# UserInterface.net
KiCad netlist of a schematic drawn in Altium Designer
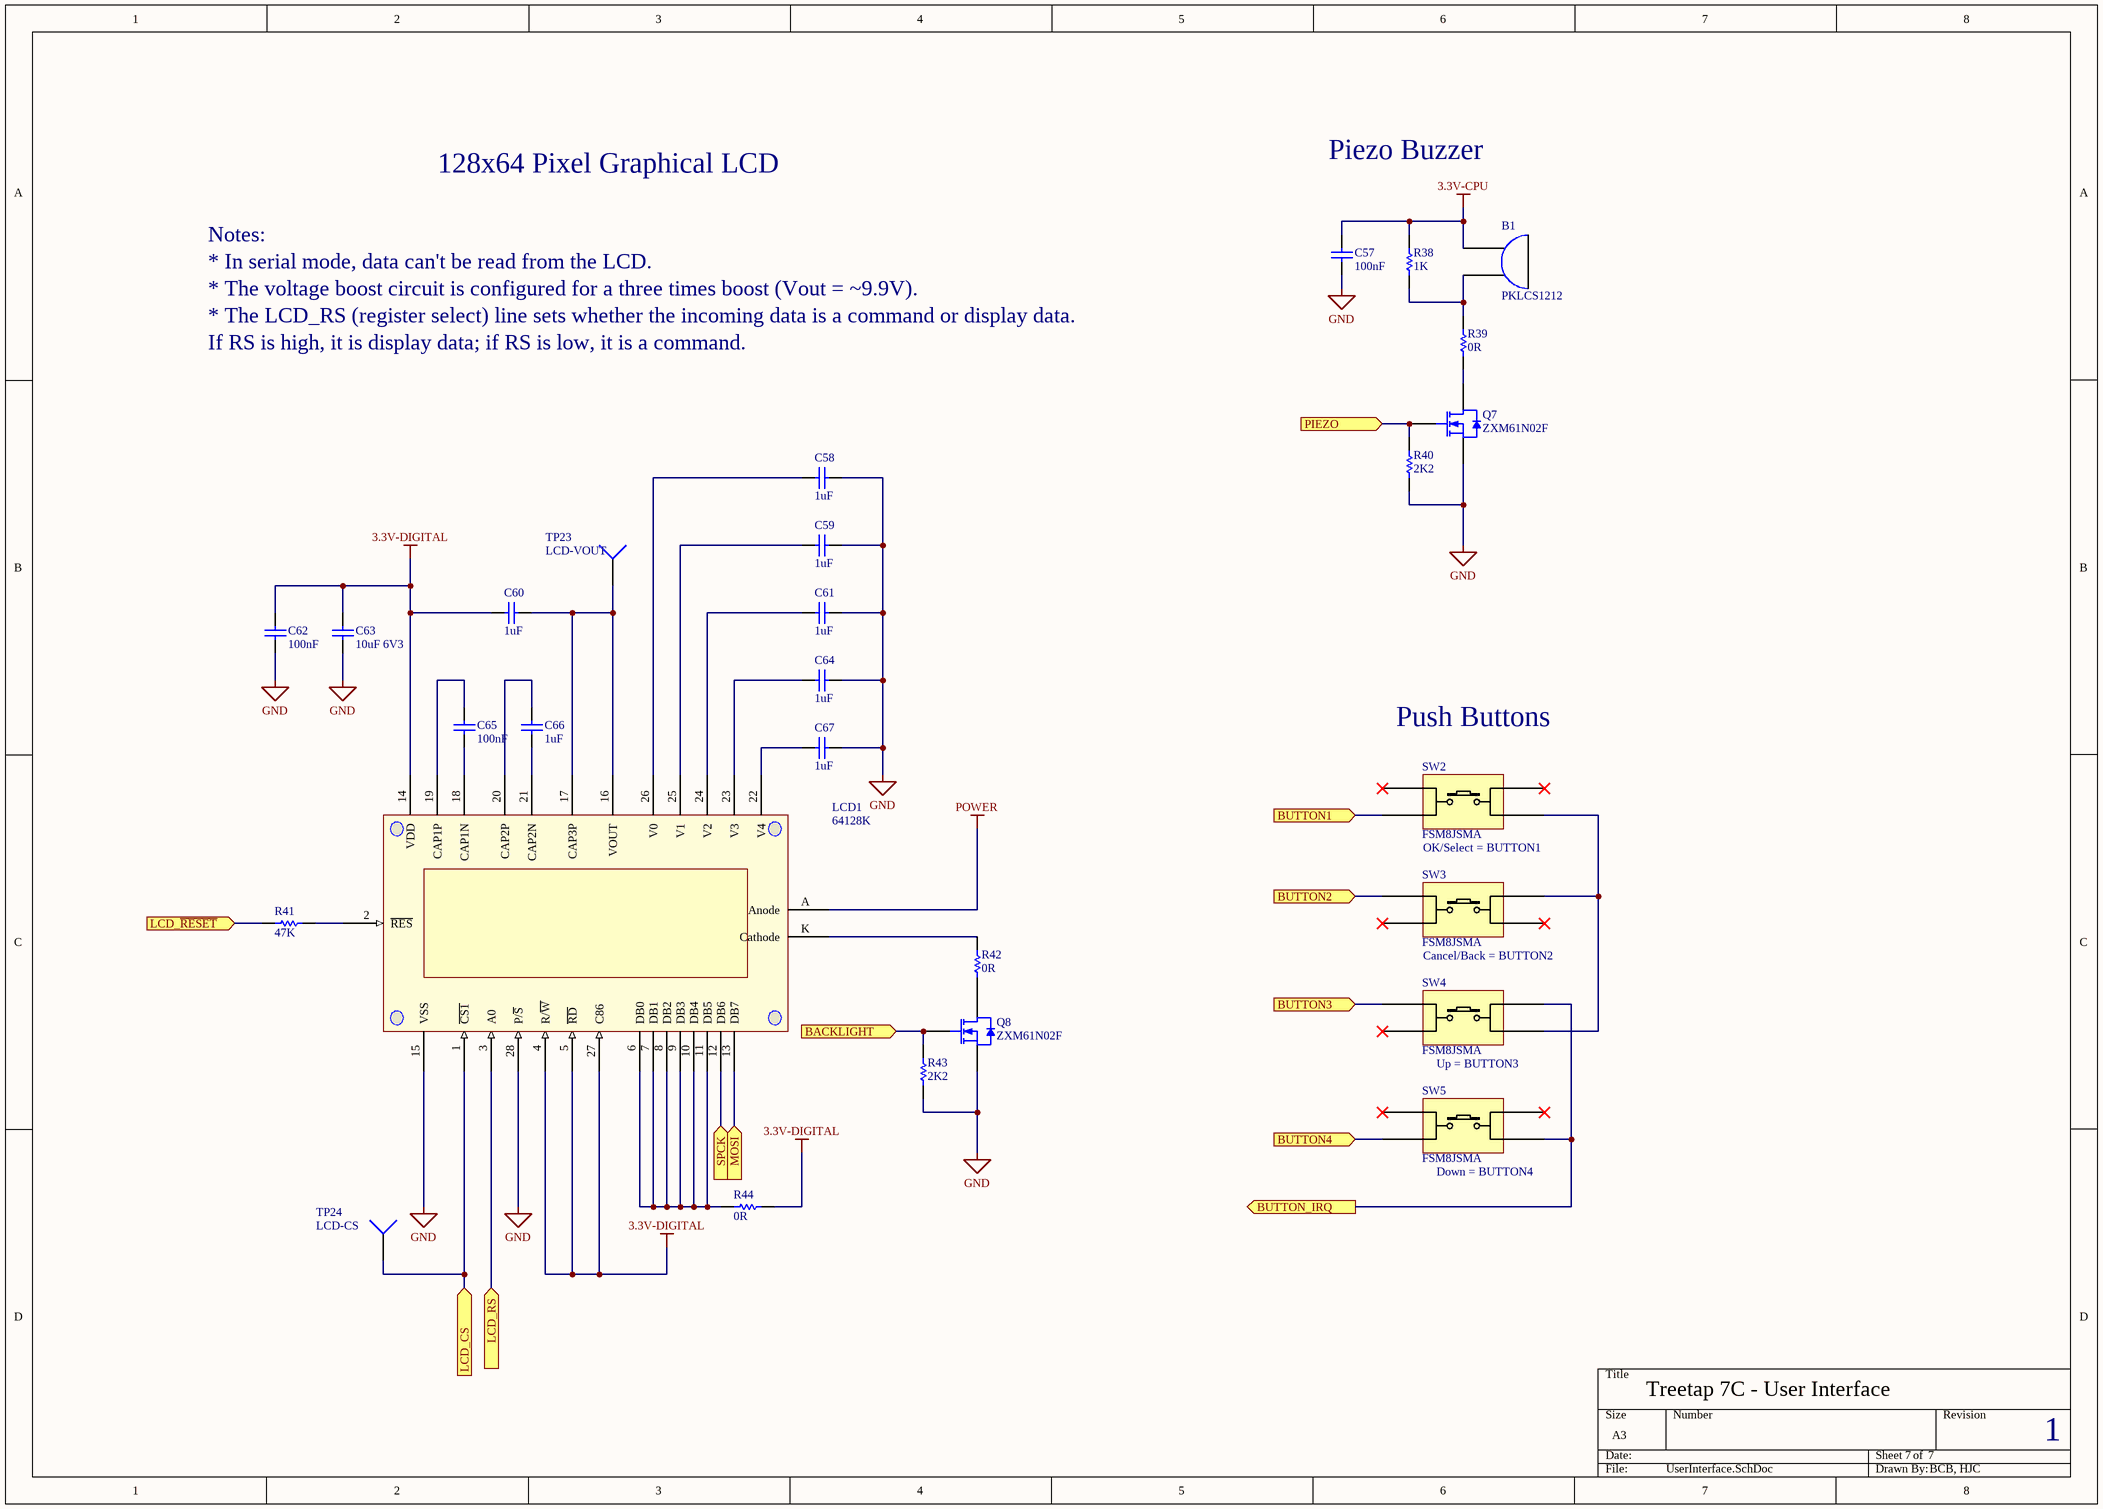
[diagram p0: UserInterface.SchDoc]

(export (version "E")
  (design (tool "Eeschema 10.0.6"))
  (components
    (comp (ref "B1")
      (value "PKLCS1212")
      (footprint "PKSCL1212")
      (description "4kHz surface mount piezo")
      (fields (field (name "MANUFACTURER") "Murata") (field (name "PART NUMBER") "PKLCS1212E4001-R1"))
      (libsource (lib "TreetapParts") (part "PKLCS1212"))
    )
    (comp (ref "C57")
      (value "100nF")
      (footprint "CC0603")
      (description "0603 Capacitor")
      (fields (field (name "PART NUMBER") "100nF_CC0603"))
      (libsource (lib "ECE_Component_Library_2") (part "100nF_CC0603"))
    )
    (comp (ref "C58")
      (value "1uF")
      (footprint "CC0603")
      (description "1uF 25V 0603 ceramic capacitor")
      (fields (field (name "MANUFACTURER") "Kemet") (field (name "PART NUMBER") "C0603C105K3PAC"))
      (libsource (lib "TreetapParts") (part "1uF_0603_25V_ceramic"))
    )
    (comp (ref "C59")
      (value "1uF")
      (footprint "CC0603")
      (description "1uF 25V 0603 ceramic capacitor")
      (fields (field (name "MANUFACTURER") "Kemet") (field (name "PART NUMBER") "C0603C105K3PAC"))
      (libsource (lib "TreetapParts") (part "1uF_0603_25V_ceramic"))
    )
    (comp (ref "C60")
      (value "1uF")
      (footprint "CC0603")
      (description "1uF 25V 0603 ceramic capacitor")
      (fields (field (name "MANUFACTURER") "Kemet") (field (name "PART NUMBER") "C0603C105K3PAC"))
      (libsource (lib "TreetapParts") (part "1uF_0603_25V_ceramic"))
    )
    (comp (ref "C61")
      (value "1uF")
      (footprint "CC0603")
      (description "1uF 25V 0603 ceramic capacitor")
      (fields (field (name "MANUFACTURER") "Kemet") (field (name "PART NUMBER") "C0603C105K3PAC"))
      (libsource (lib "TreetapParts") (part "1uF_0603_25V_ceramic"))
    )
    (comp (ref "C62")
      (value "100nF")
      (footprint "CC0603")
      (description "0603 Capacitor")
      (fields (field (name "PART NUMBER") "100nF_CC0603"))
      (libsource (lib "ECE_Component_Library_2") (part "100nF_CC0603"))
    )
    (comp (ref "C63")
      (value "10uF 6V3")
      (footprint "CC0603")
      (description "10uF 6.3V 0603 ceramic capacitor")
      (fields (field (name "MANUFACTURER") "Multicomp") (field (name "PART NUMBER") "MCCA000517"))
      (libsource (lib "TreetapParts") (part "10uF_CC0603_6V3"))
    )
    (comp (ref "C64")
      (value "1uF")
      (footprint "CC0603")
      (description "1uF 25V 0603 ceramic capacitor")
      (fields (field (name "MANUFACTURER") "Kemet") (field (name "PART NUMBER") "C0603C105K3PAC"))
      (libsource (lib "TreetapParts") (part "1uF_0603_25V_ceramic"))
    )
    (comp (ref "C65")
      (value "100nF")
      (footprint "CC0603")
      (description "0603 Capacitor")
      (fields (field (name "PART NUMBER") "100nF_CC0603"))
      (libsource (lib "ECE_Component_Library_2") (part "100nF_CC0603"))
    )
    (comp (ref "C66")
      (value "1uF")
      (footprint "CC0603")
      (description "1uF 25V 0603 ceramic capacitor")
      (fields (field (name "MANUFACTURER") "Kemet") (field (name "PART NUMBER") "C0603C105K3PAC"))
      (libsource (lib "TreetapParts") (part "1uF_0603_25V_ceramic"))
    )
    (comp (ref "C67")
      (value "1uF")
      (footprint "CC0603")
      (description "1uF 25V 0603 ceramic capacitor")
      (fields (field (name "MANUFACTURER") "Kemet") (field (name "PART NUMBER") "C0603C105K3PAC"))
      (libsource (lib "TreetapParts") (part "1uF_0603_25V_ceramic"))
    )
    (comp (ref "LCD1")
      (value "64128K")
      (footprint "64128K")
      (description "64x128 COG LCD module")
      (fields (field (name "PART NUMBER") "64128K-FC-BW-3") (field (name "MANUFACTURER") "Displaytech"))
      (libsource (lib "TreetapParts") (part "64128K"))
    )
    (comp (ref "Q7")
      (value "ZXM61N02F")
      (footprint "SOT-23")
      (description "20V N-channel enhancement mode MOSFET")
      (fields (field (name "MANUFACTURER") "Zetex"))
      (libsource (lib "TreetapParts") (part "ZXM61N02F"))
    )
    (comp (ref "Q8")
      (value "ZXM61N02F")
      (footprint "SOT-23")
      (description "20V N-channel enhancement mode MOSFET")
      (fields (field (name "MANUFACTURER") "Zetex"))
      (libsource (lib "TreetapParts") (part "ZXM61N02F"))
    )
    (comp (ref "R38")
      (value "1K")
      (footprint "R0603")
      (description "0603 Resistor")
      (fields (field (name "PART NUMBER") "1K_R0603"))
      (libsource (lib "ECE_Component_Library_2") (part "1K_R0603"))
    )
    (comp (ref "R39")
      (value "0R")
      (footprint "R0603")
      (description "0603 Resistor")
      (fields (field (name "PART NUMBER") "0R_R0603"))
      (libsource (lib "ECE_Component_Library_2") (part "0R_R0603"))
    )
    (comp (ref "R40")
      (value "2K2")
      (footprint "R0603")
      (description "0603 Resistor")
      (fields (field (name "PART NUMBER") "2K2_R0603"))
      (libsource (lib "ECE_Component_Library_2") (part "2K2_R0603"))
    )
    (comp (ref "R41")
      (value "47K")
      (footprint "R0603")
      (description "0603 Resistor")
      (fields (field (name "PART NUMBER") "47K_R0603"))
      (libsource (lib "ECE_Component_Library_2") (part "47K_R0603"))
    )
    (comp (ref "R42")
      (value "0R")
      (footprint "R0603")
      (description "0603 Resistor")
      (fields (field (name "PART NUMBER") "0R_R0603"))
      (libsource (lib "ECE_Component_Library_2") (part "0R_R0603"))
    )
    (comp (ref "R43")
      (value "2K2")
      (footprint "R0603")
      (description "0603 Resistor")
      (fields (field (name "PART NUMBER") "2K2_R0603"))
      (libsource (lib "ECE_Component_Library_2") (part "2K2_R0603"))
    )
    (comp (ref "R44")
      (value "0R")
      (footprint "R0603")
      (description "0603 Resistor")
      (fields (field (name "PART NUMBER") "0R_R0603"))
      (libsource (lib "ECE_Component_Library_2") (part "0R_R0603"))
    )
    (comp (ref "SW2")
      (value "FSM8JSMA")
      (footprint "FSM8JSMA")
      (description "DPST SMD Switch")
      (fields (field (name "MANUFACTURER") "Tyco Electronics"))
      (libsource (lib "TreetapParts") (part "FSM8JSMA"))
    )
    (comp (ref "SW3")
      (value "FSM8JSMA")
      (footprint "FSM8JSMA")
      (description "DPST SMD Switch")
      (fields (field (name "MANUFACTURER") "Tyco Electronics"))
      (libsource (lib "TreetapParts") (part "FSM8JSMA"))
    )
    (comp (ref "SW4")
      (value "FSM8JSMA")
      (footprint "FSM8JSMA")
      (description "DPST SMD Switch")
      (fields (field (name "MANUFACTURER") "Tyco Electronics"))
      (libsource (lib "TreetapParts") (part "FSM8JSMA"))
    )
    (comp (ref "SW5")
      (value "FSM8JSMA")
      (footprint "FSM8JSMA")
      (description "DPST SMD Switch")
      (fields (field (name "MANUFACTURER") "Tyco Electronics"))
      (libsource (lib "TreetapParts") (part "FSM8JSMA"))
    )
    (comp (ref "TP23")
      (value "LCD-VOUT")
      (footprint "SMTP_1")
      (description "Test point hook (surface mount)")
      (fields (field (name "MANUFACTURER") "Harwin") (field (name "PART NUMBER") "S1751-46"))
      (libsource (lib "TreetapParts") (part "SMTestPoint"))
    )
    (comp (ref "TP24")
      (value "LCD-CS")
      (footprint "SMTP_1")
      (description "Test point hook (surface mount)")
      (fields (field (name "MANUFACTURER") "Harwin") (field (name "PART NUMBER") "S1751-46"))
      (libsource (lib "TreetapParts") (part "SMTestPoint"))
    )
  )
  (nets
    (net (code "1") (name "/BACKLIGHT") (class "Default")
      (node (ref "Q8") (pin "1") (pinfunction "G_1") (pintype "passive"))
      (node (ref "R43") (pin "2") (pinfunction "2_2") (pintype "passive"))
    )
    (net (code "2") (name "/BUTTON1") (class "Default")
      (node (ref "SW2") (pin "2") (pinfunction "2_2") (pintype "passive"))
    )
    (net (code "3") (name "/BUTTON2") (class "Default")
      (node (ref "SW3") (pin "1") (pinfunction "1_1") (pintype "passive"))
    )
    (net (code "4") (name "/BUTTON3") (class "Default")
      (node (ref "SW4") (pin "1") (pinfunction "1_1") (pintype "passive"))
    )
    (net (code "5") (name "/BUTTON4") (class "Default")
      (node (ref "SW5") (pin "2") (pinfunction "2_2") (pintype "passive"))
    )
    (net (code "6") (name "/BUTTON_IRQ") (class "Default")
      (node (ref "SW4") (pin "4") (pinfunction "4_4") (pintype "passive"))
      (node (ref "SW5") (pin "3") (pinfunction "3_3") (pintype "passive"))
    )
    (net (code "7") (name "/LCD_CS") (class "Default")
      (node (ref "LCD1") (pin "1") (pinfunction "~{CS1}_1") (pintype "input"))
      (node (ref "TP24") (pin "1") (pinfunction "1_1") (pintype "passive"))
    )
    (net (code "8") (name "/LCD_RS") (class "Default")
      (node (ref "LCD1") (pin "3") (pinfunction "A0_3") (pintype "input"))
    )
    (net (code "9") (name "/LCD_~{RESET}") (class "Default")
      (node (ref "R41") (pin "1") (pinfunction "1_1") (pintype "passive"))
    )
    (net (code "10") (name "/MOSI") (class "Default")
      (node (ref "LCD1") (pin "13") (pinfunction "DB7_13") (pintype "passive"))
    )
    (net (code "11") (name "/PIEZO") (class "Default")
      (node (ref "Q7") (pin "1") (pinfunction "G_1") (pintype "passive"))
      (node (ref "R40") (pin "2") (pinfunction "2_2") (pintype "passive"))
    )
    (net (code "12") (name "/SPCK") (class "Default")
      (node (ref "LCD1") (pin "12") (pinfunction "DB6_12") (pintype "passive"))
    )
    (net (code "13") (name "3.3V-CPU") (class "Default")
      (node (ref "B1") (pin "0") (pinfunction "0_0") (pintype "passive"))
      (node (ref "C57") (pin "2") (pinfunction "2_2") (pintype "passive"))
      (node (ref "R38") (pin "2") (pinfunction "2_2") (pintype "passive"))
    )
    (net (code "14") (name "3.3V-DIGITAL") (class "Default")
      (node (ref "C60") (pin "2") (pinfunction "2_2") (pintype "passive"))
      (node (ref "C62") (pin "2") (pinfunction "2_2") (pintype "passive"))
      (node (ref "C63") (pin "2") (pinfunction "2_2") (pintype "passive"))
      (node (ref "LCD1") (pin "14") (pinfunction "VDD_14") (pintype "power_in"))
      (node (ref "LCD1") (pin "27") (pinfunction "C86_27") (pintype "input"))
      (node (ref "LCD1") (pin "4") (pinfunction "R/~{W}_4") (pintype "input"))
      (node (ref "LCD1") (pin "5") (pinfunction "~{RD}_5") (pintype "input"))
      (node (ref "R44") (pin "2") (pinfunction "2_2") (pintype "passive"))
    )
    (net (code "15") (name "GND") (class "Default")
      (node (ref "C57") (pin "1") (pinfunction "1_1") (pintype "passive"))
      (node (ref "C58") (pin "1") (pinfunction "1_1") (pintype "passive"))
      (node (ref "C59") (pin "1") (pinfunction "1_1") (pintype "passive"))
      (node (ref "C61") (pin "1") (pinfunction "1_1") (pintype "passive"))
      (node (ref "C62") (pin "1") (pinfunction "1_1") (pintype "passive"))
      (node (ref "C63") (pin "1") (pinfunction "1_1") (pintype "passive"))
      (node (ref "C64") (pin "1") (pinfunction "1_1") (pintype "passive"))
      (node (ref "C67") (pin "1") (pinfunction "1_1") (pintype "passive"))
      (node (ref "LCD1") (pin "15") (pinfunction "VSS_15") (pintype "passive"))
      (node (ref "LCD1") (pin "28") (pinfunction "P/~{S}_28") (pintype "input"))
      (node (ref "Q7") (pin "2") (pinfunction "S_2") (pintype "passive"))
      (node (ref "Q8") (pin "2") (pinfunction "S_2") (pintype "passive"))
      (node (ref "R40") (pin "1") (pinfunction "1_1") (pintype "passive"))
      (node (ref "R43") (pin "1") (pinfunction "1_1") (pintype "passive"))
    )
    (net (code "16") (name "Net-(B1-Pad1)") (class "Default")
      (node (ref "B1") (pin "1") (pinfunction "1_1") (pintype "passive"))
      (node (ref "R38") (pin "1") (pinfunction "1_1") (pintype "passive"))
      (node (ref "R39") (pin "2") (pinfunction "2_2") (pintype "passive"))
    )
    (net (code "17") (name "Net-(LCD1-CAP1N)") (class "Default")
      (node (ref "C65") (pin "1") (pinfunction "1_1") (pintype "passive"))
      (node (ref "LCD1") (pin "18") (pinfunction "CAP1N_18") (pintype "passive"))
    )
    (net (code "18") (name "Net-(LCD1-CAP1P)") (class "Default")
      (node (ref "C65") (pin "2") (pinfunction "2_2") (pintype "passive"))
      (node (ref "LCD1") (pin "19") (pinfunction "CAP1P_19") (pintype "passive"))
    )
    (net (code "19") (name "Net-(LCD1-CAP2N)") (class "Default")
      (node (ref "C66") (pin "1") (pinfunction "1_1") (pintype "passive"))
      (node (ref "LCD1") (pin "21") (pinfunction "CAP2N_21") (pintype "passive"))
    )
    (net (code "20") (name "Net-(LCD1-CAP2P)") (class "Default")
      (node (ref "C66") (pin "2") (pinfunction "2_2") (pintype "passive"))
      (node (ref "LCD1") (pin "20") (pinfunction "CAP2P_20") (pintype "passive"))
    )
    (net (code "21") (name "Net-(LCD1-CAP3P)") (class "Default")
      (node (ref "C60") (pin "1") (pinfunction "1_1") (pintype "passive"))
      (node (ref "LCD1") (pin "16") (pinfunction "VOUT_16") (pintype "passive"))
      (node (ref "LCD1") (pin "17") (pinfunction "CAP3P_17") (pintype "passive"))
      (node (ref "TP23") (pin "1") (pinfunction "1_1") (pintype "passive"))
    )
    (net (code "22") (name "Net-(LCD1-Cathode)") (class "Default")
      (node (ref "LCD1") (pin "K") (pinfunction "Cathode_K") (pintype "passive"))
      (node (ref "R42") (pin "2") (pinfunction "2_2") (pintype "passive"))
    )
    (net (code "23") (name "Net-(LCD1-DB0)") (class "Default")
      (node (ref "LCD1") (pin "10") (pinfunction "DB4_10") (pintype "passive"))
      (node (ref "LCD1") (pin "11") (pinfunction "DB5_11") (pintype "passive"))
      (node (ref "LCD1") (pin "6") (pinfunction "DB0_6") (pintype "passive"))
      (node (ref "LCD1") (pin "7") (pinfunction "DB1_7") (pintype "passive"))
      (node (ref "LCD1") (pin "8") (pinfunction "DB2_8") (pintype "passive"))
      (node (ref "LCD1") (pin "9") (pinfunction "DB3_9") (pintype "passive"))
      (node (ref "R44") (pin "1") (pinfunction "1_1") (pintype "passive"))
    )
    (net (code "24") (name "Net-(LCD1-V0)") (class "Default")
      (node (ref "C58") (pin "2") (pinfunction "2_2") (pintype "passive"))
      (node (ref "LCD1") (pin "26") (pinfunction "V0_26") (pintype "passive"))
    )
    (net (code "25") (name "Net-(LCD1-V1)") (class "Default")
      (node (ref "C59") (pin "2") (pinfunction "2_2") (pintype "passive"))
      (node (ref "LCD1") (pin "25") (pinfunction "V1_25") (pintype "passive"))
    )
    (net (code "26") (name "Net-(LCD1-V2)") (class "Default")
      (node (ref "C61") (pin "2") (pinfunction "2_2") (pintype "passive"))
      (node (ref "LCD1") (pin "24") (pinfunction "V2_24") (pintype "passive"))
    )
    (net (code "27") (name "Net-(LCD1-V3)") (class "Default")
      (node (ref "C64") (pin "2") (pinfunction "2_2") (pintype "passive"))
      (node (ref "LCD1") (pin "23") (pinfunction "V3_23") (pintype "passive"))
    )
    (net (code "28") (name "Net-(LCD1-V4)") (class "Default")
      (node (ref "C67") (pin "2") (pinfunction "2_2") (pintype "passive"))
      (node (ref "LCD1") (pin "22") (pinfunction "V4_22") (pintype "passive"))
    )
    (net (code "29") (name "Net-(LCD1-~{RES})") (class "Default")
      (node (ref "LCD1") (pin "2") (pinfunction "~{RES}_2") (pintype "input"))
      (node (ref "R41") (pin "2") (pinfunction "2_2") (pintype "passive"))
    )
    (net (code "30") (name "Net-(Q7-D)") (class "Default")
      (node (ref "Q7") (pin "3") (pinfunction "D_3") (pintype "passive"))
      (node (ref "R39") (pin "1") (pinfunction "1_1") (pintype "passive"))
    )
    (net (code "31") (name "Net-(Q8-D)") (class "Default")
      (node (ref "Q8") (pin "3") (pinfunction "D_3") (pintype "passive"))
      (node (ref "R42") (pin "1") (pinfunction "1_1") (pintype "passive"))
    )
    (net (code "32") (name "Net-(SW2-Pad3)") (class "Default")
      (node (ref "SW2") (pin "3") (pinfunction "3_3") (pintype "passive"))
      (node (ref "SW3") (pin "4") (pinfunction "4_4") (pintype "passive"))
      (node (ref "SW4") (pin "3") (pinfunction "3_3") (pintype "passive"))
    )
    (net (code "33") (name "POWER") (class "Default")
      (node (ref "LCD1") (pin "A") (pinfunction "Anode_A") (pintype "passive"))
    )
    (net (code "34") (name "unconnected-(SW2-Pad1)") (class "Default")
      (node (ref "SW2") (pin "1") (pinfunction "1_1") (pintype "passive+no_connect"))
    )
    (net (code "35") (name "unconnected-(SW2-Pad4)") (class "Default")
      (node (ref "SW2") (pin "4") (pinfunction "4_4") (pintype "passive+no_connect"))
    )
    (net (code "36") (name "unconnected-(SW3-Pad2)") (class "Default")
      (node (ref "SW3") (pin "2") (pinfunction "2_2") (pintype "passive+no_connect"))
    )
    (net (code "37") (name "unconnected-(SW3-Pad3)") (class "Default")
      (node (ref "SW3") (pin "3") (pinfunction "3_3") (pintype "passive+no_connect"))
    )
    (net (code "38") (name "unconnected-(SW4-Pad2)") (class "Default")
      (node (ref "SW4") (pin "2") (pinfunction "2_2") (pintype "passive+no_connect"))
    )
    (net (code "39") (name "unconnected-(SW5-Pad1)") (class "Default")
      (node (ref "SW5") (pin "1") (pinfunction "1_1") (pintype "passive+no_connect"))
    )
    (net (code "40") (name "unconnected-(SW5-Pad4)") (class "Default")
      (node (ref "SW5") (pin "4") (pinfunction "4_4") (pintype "passive+no_connect"))
    )
  )
)
